# led_ppm_display_w_gp_mirrored.net
KiCad netlist of a schematic drawn in EAGLE
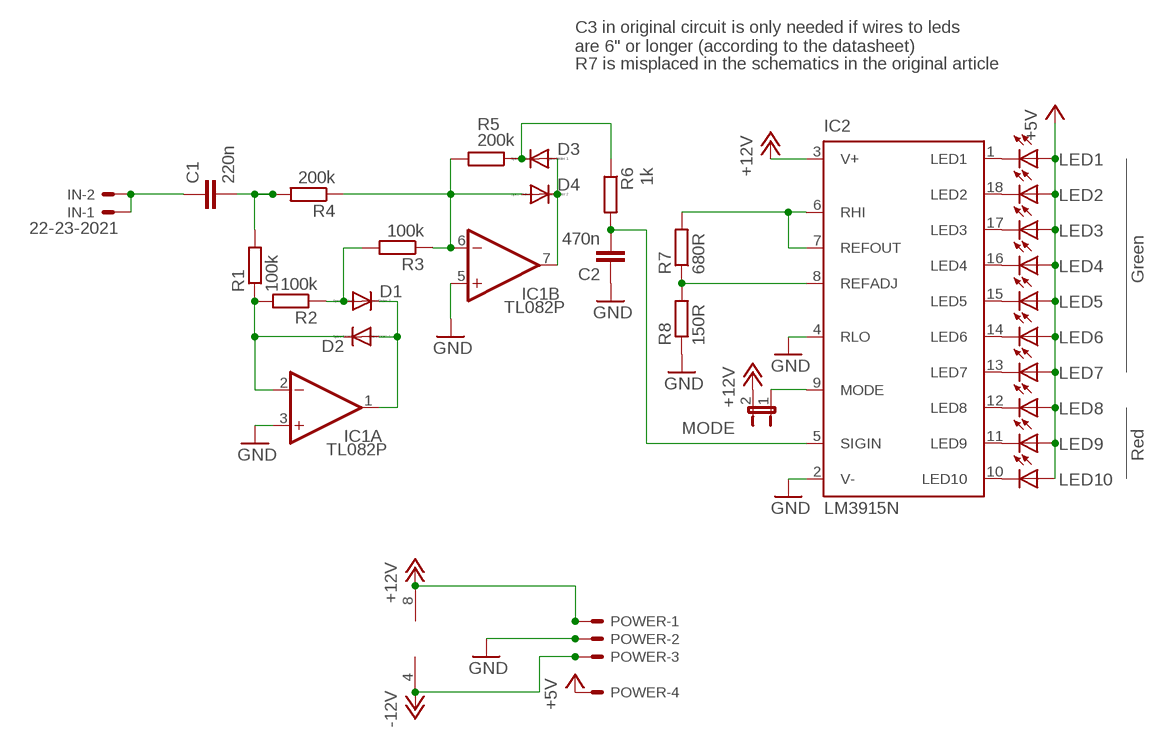
[diagram p0: schematic, sheet 1]

(export (version "E")
  (design (tool "Eeschema 10.0.6"))
  (components
    (comp (ref "C1")
      (value "220n")
      (footprint "eagle-import:C050-025X075")
      (libsource (lib "eagle-import") (part "C-EU050-025X075"))
    )
    (comp (ref "C2")
      (value "470n")
      (footprint "eagle-import:C050-025X075")
      (libsource (lib "eagle-import") (part "C-EU050-025X075"))
    )
    (comp (ref "D1")
      (value "1N4148DOJ35-5")
      (footprint "eagle-import:DO35-5J")
      (libsource (lib "eagle-import") (part "1N4148DOJ35-5"))
    )
    (comp (ref "D2")
      (value "1N4148DOJ35-5")
      (footprint "eagle-import:DO35-5J")
      (libsource (lib "eagle-import") (part "1N4148DOJ35-5"))
    )
    (comp (ref "D3")
      (value "1N4148DOJ35-5")
      (footprint "eagle-import:DO35-5J")
      (libsource (lib "eagle-import") (part "1N4148DOJ35-5"))
    )
    (comp (ref "D4")
      (value "1N4148DOJ35-5")
      (footprint "eagle-import:DO35-5J")
      (libsource (lib "eagle-import") (part "1N4148DOJ35-5"))
    )
    (comp (ref "IC1")
      (value "TL082P")
      (footprint "eagle-import:DIL08")
      (libsource (lib "eagle-import") (part "TL082P"))
    )
    (comp (ref "IC2")
      (value "LM3915N")
      (footprint "eagle-import:DIL18")
      (libsource (lib "eagle-import") (part "LM391N5"))
    )
    (comp (ref "IN")
      (value "22-23-2021")
      (footprint "eagle-import:22-23-2021")
      (fields (field (name "MF") "MOLEX"))
      (libsource (lib "eagle-import") (part "22-23-2021"))
    )
    (comp (ref "LED1")
      (value "LED3MM")
      (footprint "eagle-import:LED3MM")
      (libsource (lib "eagle-import") (part "LED3MM"))
    )
    (comp (ref "LED2")
      (value "LED3MM")
      (footprint "eagle-import:LED3MM")
      (libsource (lib "eagle-import") (part "LED3MM"))
    )
    (comp (ref "LED3")
      (value "LED3MM")
      (footprint "eagle-import:LED3MM")
      (libsource (lib "eagle-import") (part "LED3MM"))
    )
    (comp (ref "LED4")
      (value "LED3MM")
      (footprint "eagle-import:LED3MM")
      (libsource (lib "eagle-import") (part "LED3MM"))
    )
    (comp (ref "LED5")
      (value "LED3MM")
      (footprint "eagle-import:LED3MM")
      (libsource (lib "eagle-import") (part "LED3MM"))
    )
    (comp (ref "LED6")
      (value "LED3MM")
      (footprint "eagle-import:LED3MM")
      (libsource (lib "eagle-import") (part "LED3MM"))
    )
    (comp (ref "LED7")
      (value "LED3MM")
      (footprint "eagle-import:LED3MM")
      (libsource (lib "eagle-import") (part "LED3MM"))
    )
    (comp (ref "LED8")
      (value "LED3MM")
      (footprint "eagle-import:LED3MM")
      (libsource (lib "eagle-import") (part "LED3MM"))
    )
    (comp (ref "LED9")
      (value "LED3MM")
      (footprint "eagle-import:LED3MM")
      (libsource (lib "eagle-import") (part "LED3MM"))
    )
    (comp (ref "LED10")
      (value "LED3MM")
      (footprint "eagle-import:LED3MM")
      (libsource (lib "eagle-import") (part "LED3MM"))
    )
    (comp (ref "MODE")
      (value "JP1E")
      (footprint "eagle-import:JP1")
      (libsource (lib "eagle-import") (part "JP1E"))
    )
    (comp (ref "POWER")
      (value "KK-156-4")
      (footprint "eagle-import:KK-156-4")
      (libsource (lib "eagle-import") (part "KK-156-4"))
    )
    (comp (ref "R1")
      (value "100k")
      (footprint "eagle-import:0207_7")
      (libsource (lib "eagle-import") (part "R-EU_0207/7"))
    )
    (comp (ref "R2")
      (value "100k")
      (footprint "eagle-import:0207_7")
      (libsource (lib "eagle-import") (part "R-EU_0207/7"))
    )
    (comp (ref "R3")
      (value "100k")
      (footprint "eagle-import:0207_7")
      (libsource (lib "eagle-import") (part "R-EU_0207/7"))
    )
    (comp (ref "R4")
      (value "200k")
      (footprint "eagle-import:0207_7")
      (libsource (lib "eagle-import") (part "R-EU_0207/7"))
    )
    (comp (ref "R5")
      (value "200k")
      (footprint "eagle-import:0207_7")
      (libsource (lib "eagle-import") (part "R-EU_0207/7"))
    )
    (comp (ref "R6")
      (value "1k")
      (footprint "eagle-import:0207_7")
      (libsource (lib "eagle-import") (part "R-EU_0207/7"))
    )
    (comp (ref "R7")
      (value "680R")
      (footprint "eagle-import:0207_7")
      (libsource (lib "eagle-import") (part "R-EU_0207/7"))
    )
    (comp (ref "R8")
      (value "150R")
      (footprint "eagle-import:0207_7")
      (libsource (lib "eagle-import") (part "R-EU_0207/7"))
    )
  )
  (nets
    (net (code "1") (name "+5V") (class "Default")
      (node (ref "LED1") (pin "A") (pinfunction "A_A") (pintype "passive"))
      (node (ref "LED10") (pin "A") (pinfunction "A_A") (pintype "passive"))
      (node (ref "LED2") (pin "A") (pinfunction "A_A") (pintype "passive"))
      (node (ref "LED3") (pin "A") (pinfunction "A_A") (pintype "passive"))
      (node (ref "LED4") (pin "A") (pinfunction "A_A") (pintype "passive"))
      (node (ref "LED5") (pin "A") (pinfunction "A_A") (pintype "passive"))
      (node (ref "LED6") (pin "A") (pinfunction "A_A") (pintype "passive"))
      (node (ref "LED7") (pin "A") (pinfunction "A_A") (pintype "passive"))
      (node (ref "LED8") (pin "A") (pinfunction "A_A") (pintype "passive"))
      (node (ref "LED9") (pin "A") (pinfunction "A_A") (pintype "passive"))
      (node (ref "POWER") (pin "4") (pinfunction "S_4") (pintype "passive"))
    )
    (net (code "2") (name "+12V") (class "Default")
      (node (ref "IC1") (pin "8") (pinfunction "V+_8") (pintype "power_in"))
      (node (ref "IC2") (pin "3") (pinfunction "V+_3") (pintype "power_in"))
      (node (ref "MODE") (pin "2") (pinfunction "2_2") (pintype "passive"))
      (node (ref "POWER") (pin "1") (pinfunction "S_1") (pintype "passive"))
    )
    (net (code "3") (name "-12V") (class "Default")
      (node (ref "IC1") (pin "4") (pinfunction "V-_4") (pintype "power_in"))
      (node (ref "POWER") (pin "3") (pinfunction "S_3") (pintype "passive"))
    )
    (net (code "4") (name "GND") (class "Default")
      (node (ref "C2") (pin "1") (pinfunction "1_1") (pintype "passive"))
      (node (ref "IC1") (pin "3") (pinfunction "+IN_3") (pintype "input"))
      (node (ref "IC1") (pin "5") (pinfunction "+IN_5") (pintype "input"))
      (node (ref "IC2") (pin "2") (pinfunction "V-_2") (pintype "power_in"))
      (node (ref "IC2") (pin "4") (pinfunction "RLO_4") (pintype "input"))
      (node (ref "POWER") (pin "2") (pinfunction "S_2") (pintype "passive"))
      (node (ref "R8") (pin "1") (pinfunction "1_1") (pintype "passive"))
    )
    (net (code "5") (name "Net-(C1-Pad2)") (class "Default")
      (node (ref "C1") (pin "2") (pinfunction "2_2") (pintype "passive"))
      (node (ref "R1") (pin "2") (pinfunction "2_2") (pintype "passive"))
      (node (ref "R4") (pin "2") (pinfunction "2_2") (pintype "passive"))
    )
    (net (code "6") (name "Net-(D1-PadA)") (class "Default")
      (node (ref "D1") (pin "A") (pinfunction "A_A") (pintype "passive"))
      (node (ref "R2") (pin "1") (pinfunction "1_1") (pintype "passive"))
      (node (ref "R3") (pin "2") (pinfunction "2_2") (pintype "passive"))
    )
    (net (code "7") (name "Net-(D3-PadC)") (class "Default")
      (node (ref "D3") (pin "C") (pinfunction "C_C") (pintype "passive"))
      (node (ref "R5") (pin "1") (pinfunction "1_1") (pintype "passive"))
      (node (ref "R6") (pin "1") (pinfunction "1_1") (pintype "passive"))
    )
    (net (code "8") (name "Net-(IC1A--IN)") (class "Default")
      (node (ref "D2") (pin "C") (pinfunction "C_C") (pintype "passive"))
      (node (ref "IC1") (pin "2") (pinfunction "-IN_2") (pintype "input"))
      (node (ref "R1") (pin "1") (pinfunction "1_1") (pintype "passive"))
      (node (ref "R2") (pin "2") (pinfunction "2_2") (pintype "passive"))
    )
    (net (code "9") (name "Net-(IC1A-OUT)") (class "Default")
      (node (ref "D1") (pin "C") (pinfunction "C_C") (pintype "passive"))
      (node (ref "D2") (pin "A") (pinfunction "A_A") (pintype "passive"))
      (node (ref "IC1") (pin "1") (pinfunction "OUT_1") (pintype "output"))
    )
    (net (code "10") (name "Net-(IC1B--IN)") (class "Default")
      (node (ref "D4") (pin "A") (pinfunction "A_A") (pintype "passive"))
      (node (ref "IC1") (pin "6") (pinfunction "-IN_6") (pintype "input"))
      (node (ref "R3") (pin "1") (pinfunction "1_1") (pintype "passive"))
      (node (ref "R4") (pin "1") (pinfunction "1_1") (pintype "passive"))
      (node (ref "R5") (pin "2") (pinfunction "2_2") (pintype "passive"))
    )
    (net (code "11") (name "Net-(IC1B-OUT)") (class "Default")
      (node (ref "D3") (pin "A") (pinfunction "A_A") (pintype "passive"))
      (node (ref "D4") (pin "C") (pinfunction "C_C") (pintype "passive"))
      (node (ref "IC1") (pin "7") (pinfunction "OUT_7") (pintype "output"))
    )
    (net (code "12") (name "Net-(IC2-LED1)") (class "Default")
      (node (ref "IC2") (pin "1") (pinfunction "LED1_1") (pintype "output"))
      (node (ref "LED1") (pin "K") (pinfunction "C_K") (pintype "passive"))
    )
    (net (code "13") (name "Net-(IC2-LED2)") (class "Default")
      (node (ref "IC2") (pin "18") (pinfunction "LED2_18") (pintype "output"))
      (node (ref "LED2") (pin "K") (pinfunction "C_K") (pintype "passive"))
    )
    (net (code "14") (name "Net-(IC2-LED3)") (class "Default")
      (node (ref "IC2") (pin "17") (pinfunction "LED3_17") (pintype "output"))
      (node (ref "LED3") (pin "K") (pinfunction "C_K") (pintype "passive"))
    )
    (net (code "15") (name "Net-(IC2-LED4)") (class "Default")
      (node (ref "IC2") (pin "16") (pinfunction "LED4_16") (pintype "output"))
      (node (ref "LED4") (pin "K") (pinfunction "C_K") (pintype "passive"))
    )
    (net (code "16") (name "Net-(IC2-LED5)") (class "Default")
      (node (ref "IC2") (pin "15") (pinfunction "LED5_15") (pintype "output"))
      (node (ref "LED5") (pin "K") (pinfunction "C_K") (pintype "passive"))
    )
    (net (code "17") (name "Net-(IC2-LED6)") (class "Default")
      (node (ref "IC2") (pin "14") (pinfunction "LED6_14") (pintype "output"))
      (node (ref "LED6") (pin "K") (pinfunction "C_K") (pintype "passive"))
    )
    (net (code "18") (name "Net-(IC2-LED7)") (class "Default")
      (node (ref "IC2") (pin "13") (pinfunction "LED7_13") (pintype "output"))
      (node (ref "LED7") (pin "K") (pinfunction "C_K") (pintype "passive"))
    )
    (net (code "19") (name "Net-(IC2-LED8)") (class "Default")
      (node (ref "IC2") (pin "12") (pinfunction "LED8_12") (pintype "output"))
      (node (ref "LED8") (pin "K") (pinfunction "C_K") (pintype "passive"))
    )
    (net (code "20") (name "Net-(IC2-LED9)") (class "Default")
      (node (ref "IC2") (pin "11") (pinfunction "LED9_11") (pintype "output"))
      (node (ref "LED9") (pin "K") (pinfunction "C_K") (pintype "passive"))
    )
    (net (code "21") (name "Net-(IC2-LED10)") (class "Default")
      (node (ref "IC2") (pin "10") (pinfunction "LED10_10") (pintype "output"))
      (node (ref "LED10") (pin "K") (pinfunction "C_K") (pintype "passive"))
    )
    (net (code "22") (name "Net-(IC2-MODE)") (class "Default")
      (node (ref "IC2") (pin "9") (pinfunction "MODE_9") (pintype "input"))
      (node (ref "MODE") (pin "1") (pinfunction "1_1") (pintype "passive"))
    )
    (net (code "23") (name "Net-(IC2-REFADJ)") (class "Default")
      (node (ref "IC2") (pin "8") (pinfunction "REFADJ_8") (pintype "passive"))
      (node (ref "R7") (pin "1") (pinfunction "1_1") (pintype "passive"))
      (node (ref "R8") (pin "2") (pinfunction "2_2") (pintype "passive"))
    )
    (net (code "24") (name "Net-(IC2-REFOUT)") (class "Default")
      (node (ref "IC2") (pin "6") (pinfunction "RHI_6") (pintype "input"))
      (node (ref "IC2") (pin "7") (pinfunction "REFOUT_7") (pintype "output"))
      (node (ref "R7") (pin "2") (pinfunction "2_2") (pintype "passive"))
    )
    (net (code "25") (name "Net-(IC2-SIGIN)") (class "Default")
      (node (ref "C2") (pin "2") (pinfunction "2_2") (pintype "passive"))
      (node (ref "IC2") (pin "5") (pinfunction "SIGIN_5") (pintype "input"))
      (node (ref "R6") (pin "2") (pinfunction "2_2") (pintype "passive"))
    )
    (net (code "26") (name "Net-(INA-S)") (class "Default")
      (node (ref "C1") (pin "1") (pinfunction "1_1") (pintype "passive"))
      (node (ref "IN") (pin "1") (pinfunction "S_1") (pintype "passive"))
      (node (ref "IN") (pin "2") (pinfunction "S_2") (pintype "passive"))
    )
  )
)
